# oc.net
KiCad netlist of a schematic drawn in EAGLE
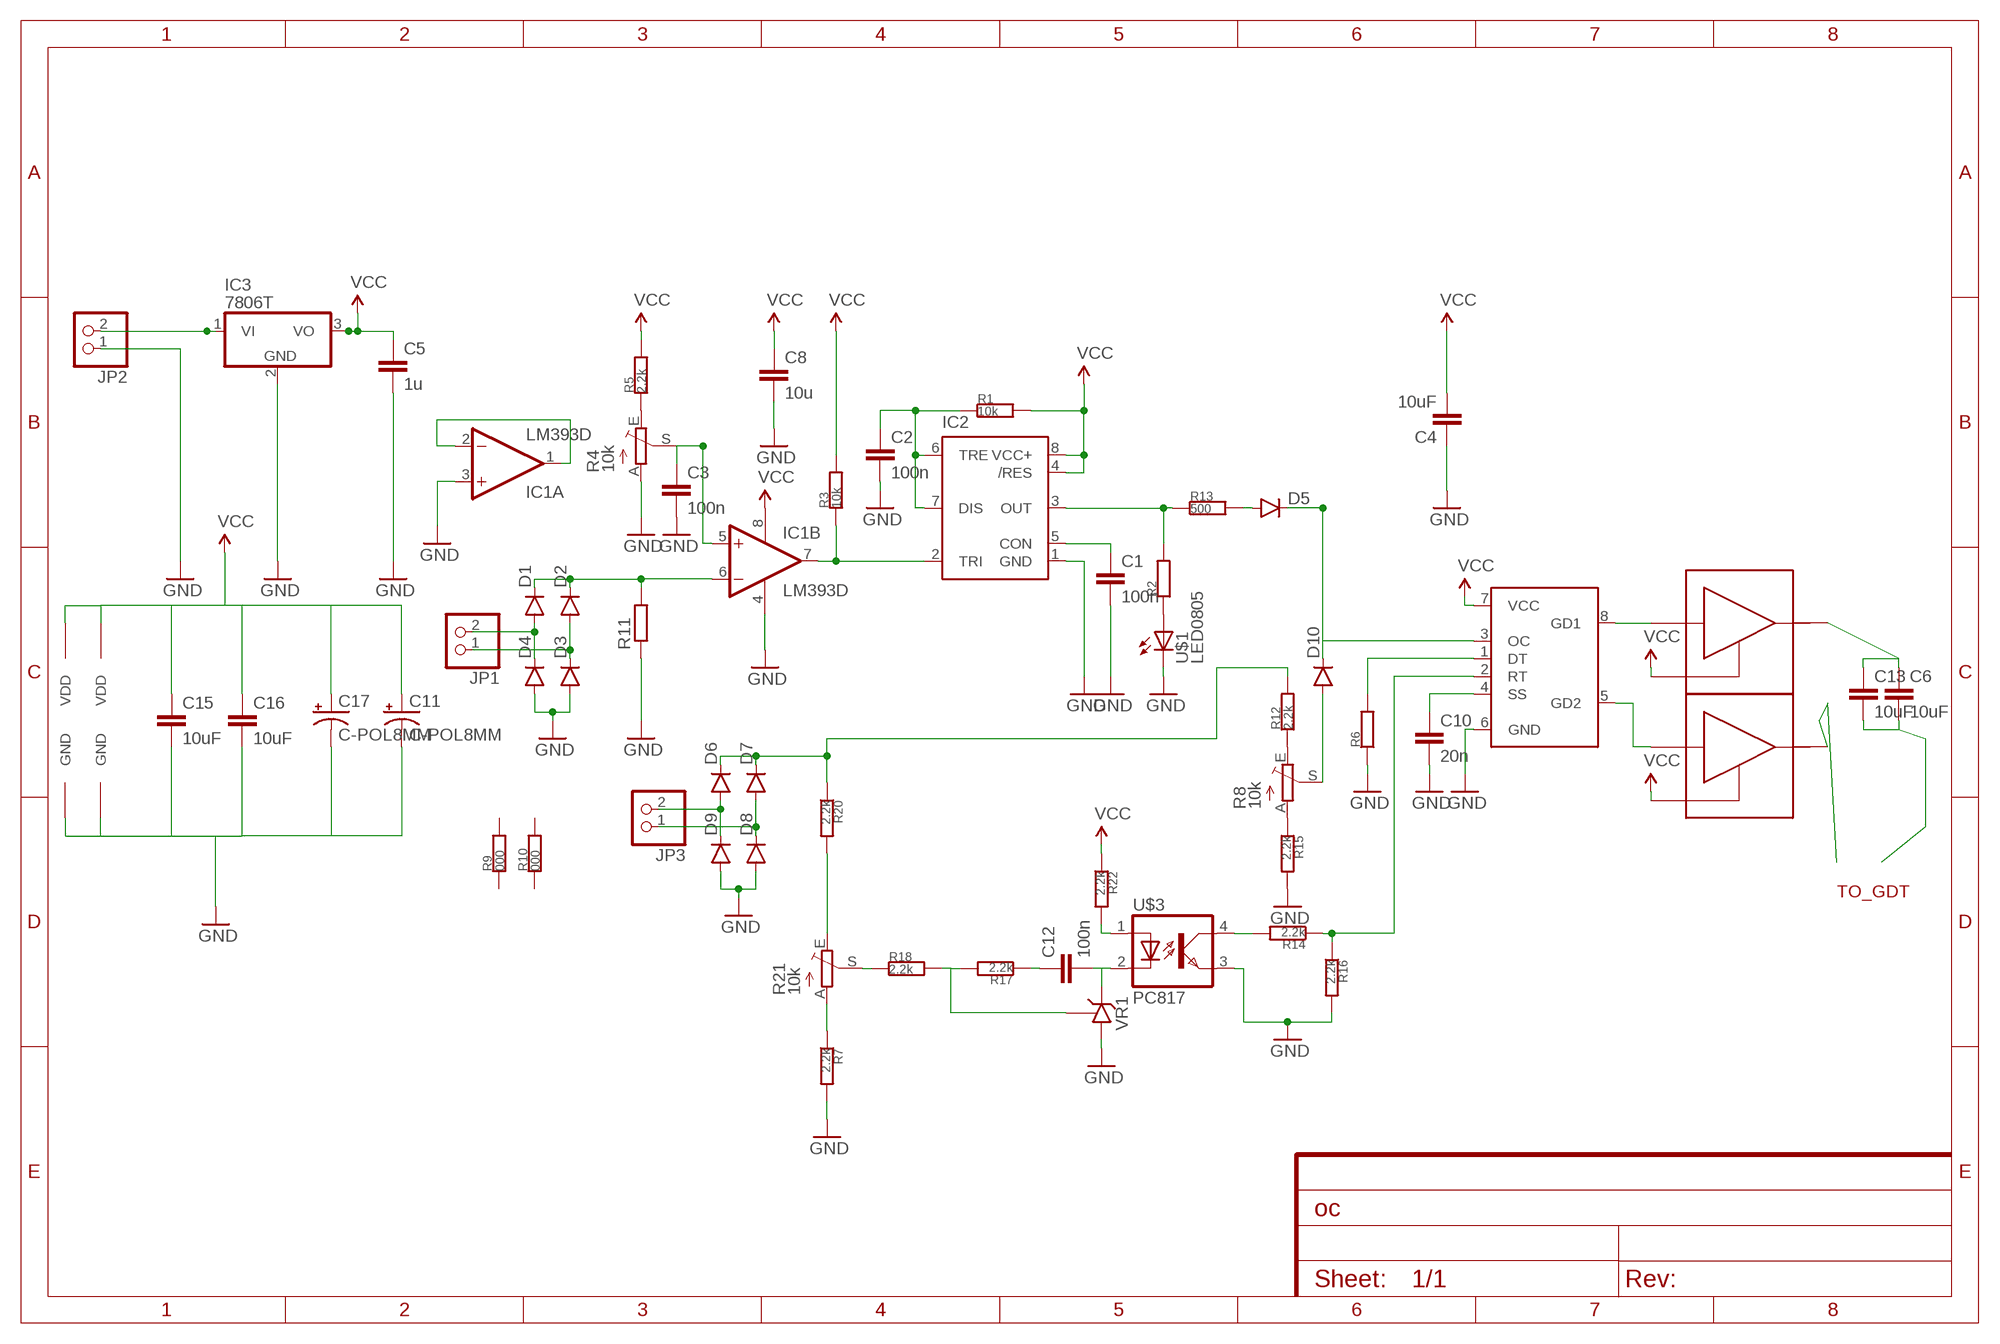
[diagram p0: schematic, sheet 1]

(export (version "E")
  (design (tool "Eeschema 10.0.6"))
  (components
    (comp (ref "C1")
      (value "100n")
      (footprint "eagle-import:C0805")
      (libsource (lib "eagle-import") (part "CC0805"))
    )
    (comp (ref "C2")
      (value "100n")
      (footprint "eagle-import:C0805")
      (libsource (lib "eagle-import") (part "CC0805"))
    )
    (comp (ref "C3")
      (value "100n")
      (footprint "eagle-import:C0603")
      (libsource (lib "eagle-import") (part "CC0603"))
    )
    (comp (ref "C4")
      (value "10uF")
      (footprint "eagle-import:1210")
      (libsource (lib "eagle-import") (part "10UF50V20%(1210)"))
    )
    (comp (ref "C5")
      (value "1u")
      (footprint "eagle-import:C0805")
      (libsource (lib "eagle-import") (part "CC0805"))
    )
    (comp (ref "C6")
      (value "10uF")
      (footprint "eagle-import:1210")
      (libsource (lib "eagle-import") (part "10UF50V20%(1210)"))
    )
    (comp (ref "C8")
      (value "10u")
      (footprint "eagle-import:C0805")
      (libsource (lib "eagle-import") (part "CC0805"))
    )
    (comp (ref "C10")
      (value "20n")
      (footprint "eagle-import:C0805")
      (libsource (lib "eagle-import") (part "CC0805"))
    )
    (comp (ref "C11")
      (value "C-POL8MM")
      (footprint "eagle-import:PCAP8")
      (libsource (lib "eagle-import") (part "C-POL8MM"))
    )
    (comp (ref "C12")
      (value "100n")
      (footprint "eagle-import:C0805")
      (libsource (lib "eagle-import") (part "CC0805"))
    )
    (comp (ref "C13")
      (value "10uF")
      (footprint "eagle-import:1210")
      (libsource (lib "eagle-import") (part "10UF50V20%(1210)"))
    )
    (comp (ref "C15")
      (value "10uF")
      (footprint "eagle-import:1210")
      (libsource (lib "eagle-import") (part "10UF50V20%(1210)"))
    )
    (comp (ref "C16")
      (value "10uF")
      (footprint "eagle-import:1210")
      (libsource (lib "eagle-import") (part "10UF50V20%(1210)"))
    )
    (comp (ref "C17")
      (value "C-POL8MM")
      (footprint "eagle-import:PCAP8")
      (libsource (lib "eagle-import") (part "C-POL8MM"))
    )
    (comp (ref "D1")
      (value "PMLL4150")
      (footprint "eagle-import:SOD80C")
      (libsource (lib "eagle-import") (part "PMLL4150"))
    )
    (comp (ref "D2")
      (value "PMLL4150")
      (footprint "eagle-import:SOD80C")
      (libsource (lib "eagle-import") (part "PMLL4150"))
    )
    (comp (ref "D3")
      (value "PMLL4150")
      (footprint "eagle-import:SOD80C")
      (libsource (lib "eagle-import") (part "PMLL4150"))
    )
    (comp (ref "D4")
      (value "PMLL4150")
      (footprint "eagle-import:SOD80C")
      (libsource (lib "eagle-import") (part "PMLL4150"))
    )
    (comp (ref "D5")
      (value "PMLL4150")
      (footprint "eagle-import:SOD80C")
      (libsource (lib "eagle-import") (part "PMLL4150"))
    )
    (comp (ref "D6")
      (value "PMLL4150")
      (footprint "eagle-import:SOD80C")
      (libsource (lib "eagle-import") (part "PMLL4150"))
    )
    (comp (ref "D7")
      (value "PMLL4150")
      (footprint "eagle-import:SOD80C")
      (libsource (lib "eagle-import") (part "PMLL4150"))
    )
    (comp (ref "D8")
      (value "PMLL4150")
      (footprint "eagle-import:SOD80C")
      (libsource (lib "eagle-import") (part "PMLL4150"))
    )
    (comp (ref "D9")
      (value "PMLL4150")
      (footprint "eagle-import:SOD80C")
      (libsource (lib "eagle-import") (part "PMLL4150"))
    )
    (comp (ref "D10")
      (value "PMLL4150")
      (footprint "eagle-import:SOD80C")
      (libsource (lib "eagle-import") (part "PMLL4150"))
    )
    (comp (ref "IC1")
      (value "LM393D")
      (footprint "eagle-import:SO08")
      (libsource (lib "eagle-import") (part "LM393D"))
    )
    (comp (ref "IC2")
      (value "NE555D")
      (footprint "eagle-import:SO08")
      (libsource (lib "eagle-import") (part "NE555D"))
    )
    (comp (ref "IC3")
      (value "7806T")
      (footprint "eagle-import:TO220H")
      (libsource (lib "eagle-import") (part "78T06"))
    )
    (comp (ref "JP1")
      (value "PINHD-1X2")
      (footprint "eagle-import:1X02")
      (libsource (lib "eagle-import") (part "PINHD-1X2"))
    )
    (comp (ref "JP2")
      (value "PINHD-1X2")
      (footprint "eagle-import:1X02")
      (libsource (lib "eagle-import") (part "PINHD-1X2"))
    )
    (comp (ref "JP3")
      (value "PINHD-1X2")
      (footprint "eagle-import:1X02")
      (libsource (lib "eagle-import") (part "PINHD-1X2"))
    )
    (comp (ref "R1")
      (value "10k")
      (footprint "eagle-import:R0805")
      (libsource (lib "eagle-import") (part "R0805"))
    )
    (comp (ref "R2")
      (value "R0805")
      (footprint "eagle-import:R0805")
      (libsource (lib "eagle-import") (part "R0805"))
    )
    (comp (ref "R3")
      (value "10k")
      (footprint "eagle-import:R0805")
      (libsource (lib "eagle-import") (part "R0805"))
    )
    (comp (ref "R4")
      (value "10k")
      (footprint "eagle-import:RJ9W")
      (libsource (lib "eagle-import") (part "TRIM_EU-RJ9W"))
    )
    (comp (ref "R5")
      (value "2.2k")
      (footprint "eagle-import:R0805")
      (libsource (lib "eagle-import") (part "R0805"))
    )
    (comp (ref "R6")
      (value "R0805")
      (footprint "eagle-import:R0805")
      (libsource (lib "eagle-import") (part "R0805"))
    )
    (comp (ref "R7")
      (value "2.2k")
      (footprint "eagle-import:R0805")
      (libsource (lib "eagle-import") (part "R0805"))
    )
    (comp (ref "R8")
      (value "10k")
      (footprint "eagle-import:RJ9W")
      (libsource (lib "eagle-import") (part "TRIM_EU-RJ9W"))
    )
    (comp (ref "R9")
      (value "000")
      (footprint "eagle-import:R1206")
      (libsource (lib "eagle-import") (part "R1206"))
    )
    (comp (ref "R10")
      (value "000")
      (footprint "eagle-import:R0805")
      (libsource (lib "eagle-import") (part "R0805"))
    )
    (comp (ref "R11")
      (value "R-EU_0617/17")
      (footprint "eagle-import:0617_17")
      (libsource (lib "eagle-import") (part "R-EU_0617/17"))
    )
    (comp (ref "R12")
      (value "2.2k")
      (footprint "eagle-import:R0805")
      (libsource (lib "eagle-import") (part "R0805"))
    )
    (comp (ref "R13")
      (value "500")
      (footprint "eagle-import:R0805")
      (libsource (lib "eagle-import") (part "R0805"))
    )
    (comp (ref "R14")
      (value "2.2k")
      (footprint "eagle-import:R0805")
      (libsource (lib "eagle-import") (part "R0805"))
    )
    (comp (ref "R15")
      (value "2.2k")
      (footprint "eagle-import:R0805")
      (libsource (lib "eagle-import") (part "R0805"))
    )
    (comp (ref "R16")
      (value "2.2k")
      (footprint "eagle-import:R0805")
      (libsource (lib "eagle-import") (part "R0805"))
    )
    (comp (ref "R17")
      (value "2.2k")
      (footprint "eagle-import:R0805")
      (libsource (lib "eagle-import") (part "R0805"))
    )
    (comp (ref "R18")
      (value "2.2k")
      (footprint "eagle-import:R0805")
      (libsource (lib "eagle-import") (part "R0805"))
    )
    (comp (ref "R20")
      (value "2.2k")
      (footprint "eagle-import:R0805")
      (libsource (lib "eagle-import") (part "R0805"))
    )
    (comp (ref "R21")
      (value "10k")
      (footprint "eagle-import:RJ9W")
      (libsource (lib "eagle-import") (part "TRIM_EU-RJ9W"))
    )
    (comp (ref "R22")
      (value "2.2k")
      (footprint "eagle-import:R0805")
      (libsource (lib "eagle-import") (part "R0805"))
    )
    (comp (ref "U$1")
      (value "LED0805")
      (footprint "eagle-import:0805-LED")
      (libsource (lib "eagle-import") (part "LED0805"))
    )
    (comp (ref "U$2")
      (value "TPS92020")
      (footprint "eagle-import:SO08")
      (libsource (lib "eagle-import") (part "TPS92020"))
    )
    (comp (ref "U$3")
      (value "PC817")
      (footprint "eagle-import:DIL4-SMD")
      (libsource (lib "eagle-import") (part "PC817"))
    )
    (comp (ref "U$7")
      (value "IXDD614")
      (footprint "eagle-import:DPACK-5")
      (libsource (lib "eagle-import") (part "IXDD614"))
    )
    (comp (ref "U$8")
      (value "IXDD614")
      (footprint "eagle-import:DPACK-5")
      (libsource (lib "eagle-import") (part "IXDD614"))
    )
    (comp (ref "VR1")
      (value "TL431CLPSO8")
      (footprint "eagle-import:SO08")
      (libsource (lib "eagle-import") (part "TL431CLPSO8"))
    )
  )
  (nets
    (net (code "1") (name "GND") (class "Default")
      (node (ref "C1") (pin "2") (pinfunction "2_2") (pintype "passive"))
      (node (ref "C10") (pin "2") (pinfunction "2_2") (pintype "passive"))
      (node (ref "C11") (pin "P$2") (pinfunction "-_P$2") (pintype "passive"))
      (node (ref "C15") (pin "2") (pinfunction "2_2") (pintype "passive"))
      (node (ref "C16") (pin "2") (pinfunction "2_2") (pintype "passive"))
      (node (ref "C17") (pin "P$2") (pinfunction "-_P$2") (pintype "passive"))
      (node (ref "C2") (pin "2") (pinfunction "2_2") (pintype "passive"))
      (node (ref "C3") (pin "2") (pinfunction "2_2") (pintype "passive"))
      (node (ref "C4") (pin "1") (pinfunction "1_1") (pintype "passive"))
      (node (ref "C5") (pin "2") (pinfunction "2_2") (pintype "passive"))
      (node (ref "C8") (pin "2") (pinfunction "2_2") (pintype "passive"))
      (node (ref "D3") (pin "A") (pinfunction "A_A") (pintype "passive"))
      (node (ref "D4") (pin "A") (pinfunction "A_A") (pintype "passive"))
      (node (ref "D8") (pin "A") (pinfunction "A_A") (pintype "passive"))
      (node (ref "D9") (pin "A") (pinfunction "A_A") (pintype "passive"))
      (node (ref "IC1") (pin "3") (pinfunction "+IN_3") (pintype "input"))
      (node (ref "IC1") (pin "4") (pinfunction "V-_4") (pintype "power_in"))
      (node (ref "IC2") (pin "1") (pinfunction "GND_1") (pintype "power_in"))
      (node (ref "IC3") (pin "2") (pinfunction "GND_2") (pintype "passive"))
      (node (ref "JP2") (pin "1") (pinfunction "1_1") (pintype "passive"))
      (node (ref "R11") (pin "1") (pinfunction "1_1") (pintype "passive"))
      (node (ref "R15") (pin "2") (pinfunction "2_2") (pintype "passive"))
      (node (ref "R16") (pin "2") (pinfunction "2_2") (pintype "passive"))
      (node (ref "R4") (pin "A") (pinfunction "A_A") (pintype "passive"))
      (node (ref "R6") (pin "1") (pinfunction "1_1") (pintype "passive"))
      (node (ref "R7") (pin "2") (pinfunction "2_2") (pintype "passive"))
      (node (ref "U$1") (pin "C") (pinfunction "C_C") (pintype "passive"))
      (node (ref "U$2") (pin "6") (pinfunction "GND_6") (pintype "bidirectional"))
      (node (ref "U$3") (pin "3") (pinfunction "EMIT_3") (pintype "passive"))
      (node (ref "U$7") (pin "3") (pinfunction "GND_3") (pintype "power_in"))
      (node (ref "U$7") (pin "6") (pinfunction "GND_6") (pintype "power_in"))
      (node (ref "U$8") (pin "3") (pinfunction "GND_3") (pintype "power_in"))
      (node (ref "U$8") (pin "6") (pinfunction "GND_6") (pintype "power_in"))
      (node (ref "VR1") (pin "2") (pinfunction "A_2") (pintype "passive"))
      (node (ref "VR1") (pin "3") (pinfunction "A_3") (pintype "passive"))
      (node (ref "VR1") (pin "6") (pinfunction "A_6") (pintype "passive"))
      (node (ref "VR1") (pin "7") (pinfunction "A_7") (pintype "passive"))
    )
    (net (code "2") (name "Net-(C12-Pad1)") (class "Default")
      (node (ref "C12") (pin "1") (pinfunction "1_1") (pintype "passive"))
      (node (ref "R17") (pin "1") (pinfunction "1_1") (pintype "passive"))
    )
    (net (code "3") (name "Net-(C13-Pad2)") (class "Default")
      (node (ref "C13") (pin "2") (pinfunction "2_2") (pintype "passive"))
      (node (ref "C6") (pin "2") (pinfunction "2_2") (pintype "passive"))
    )
    (net (code "4") (name "Net-(D1-PadA)") (class "Default")
      (node (ref "D1") (pin "A") (pinfunction "A_A") (pintype "passive"))
      (node (ref "D4") (pin "C") (pinfunction "C_C") (pintype "passive"))
      (node (ref "JP1") (pin "2") (pinfunction "2_2") (pintype "passive"))
    )
    (net (code "5") (name "Net-(D2-PadA)") (class "Default")
      (node (ref "D2") (pin "A") (pinfunction "A_A") (pintype "passive"))
      (node (ref "D3") (pin "C") (pinfunction "C_C") (pintype "passive"))
      (node (ref "JP1") (pin "1") (pinfunction "1_1") (pintype "passive"))
    )
    (net (code "6") (name "Net-(D5-PadA)") (class "Default")
      (node (ref "D5") (pin "A") (pinfunction "A_A") (pintype "passive"))
      (node (ref "R13") (pin "2") (pinfunction "2_2") (pintype "passive"))
    )
    (net (code "7") (name "Net-(D6-PadA)") (class "Default")
      (node (ref "D6") (pin "A") (pinfunction "A_A") (pintype "passive"))
      (node (ref "D9") (pin "C") (pinfunction "C_C") (pintype "passive"))
      (node (ref "JP3") (pin "2") (pinfunction "2_2") (pintype "passive"))
    )
    (net (code "8") (name "Net-(D6-PadC)") (class "Default")
      (node (ref "D6") (pin "C") (pinfunction "C_C") (pintype "passive"))
      (node (ref "D7") (pin "C") (pinfunction "C_C") (pintype "passive"))
      (node (ref "R12") (pin "2") (pinfunction "2_2") (pintype "passive"))
      (node (ref "R20") (pin "1") (pinfunction "1_1") (pintype "passive"))
    )
    (net (code "9") (name "Net-(D7-PadA)") (class "Default")
      (node (ref "D7") (pin "A") (pinfunction "A_A") (pintype "passive"))
      (node (ref "D8") (pin "C") (pinfunction "C_C") (pintype "passive"))
      (node (ref "JP3") (pin "1") (pinfunction "1_1") (pintype "passive"))
    )
    (net (code "10") (name "Net-(D10-PadA)") (class "Default")
      (node (ref "D10") (pin "A") (pinfunction "A_A") (pintype "passive"))
      (node (ref "R8") (pin "S") (pinfunction "S_S") (pintype "passive"))
    )
    (net (code "11") (name "Net-(IC1A--IN)") (class "Default")
      (node (ref "IC1") (pin "1") (pinfunction "OUT_1") (pintype "output"))
      (node (ref "IC1") (pin "2") (pinfunction "-IN_2") (pintype "input"))
    )
    (net (code "12") (name "Net-(IC1B-+IN)") (class "Default")
      (node (ref "C3") (pin "1") (pinfunction "1_1") (pintype "passive"))
      (node (ref "IC1") (pin "5") (pinfunction "+IN_5") (pintype "input"))
      (node (ref "R4") (pin "S") (pinfunction "S_S") (pintype "passive"))
    )
    (net (code "13") (name "Net-(IC1B--IN)") (class "Default")
      (node (ref "D1") (pin "C") (pinfunction "C_C") (pintype "passive"))
      (node (ref "D2") (pin "C") (pinfunction "C_C") (pintype "passive"))
      (node (ref "IC1") (pin "6") (pinfunction "-IN_6") (pintype "input"))
      (node (ref "R11") (pin "2") (pinfunction "2_2") (pintype "passive"))
    )
    (net (code "14") (name "Net-(IC1B-OUT)") (class "Default")
      (node (ref "IC1") (pin "7") (pinfunction "OUT_7") (pintype "output"))
      (node (ref "IC2") (pin "2") (pinfunction "TRI_2") (pintype "input"))
      (node (ref "R3") (pin "1") (pinfunction "1_1") (pintype "passive"))
    )
    (net (code "15") (name "Net-(IC2-CON)") (class "Default")
      (node (ref "C1") (pin "1") (pinfunction "1_1") (pintype "passive"))
      (node (ref "IC2") (pin "5") (pinfunction "CON_5") (pintype "input"))
    )
    (net (code "16") (name "Net-(IC2-DIS)") (class "Default")
      (node (ref "C2") (pin "1") (pinfunction "1_1") (pintype "passive"))
      (node (ref "IC2") (pin "6") (pinfunction "TRE_6") (pintype "input"))
      (node (ref "IC2") (pin "7") (pinfunction "DIS_7") (pintype "input"))
      (node (ref "R1") (pin "1") (pinfunction "1_1") (pintype "passive"))
    )
    (net (code "17") (name "Net-(IC2-OUT)") (class "Default")
      (node (ref "IC2") (pin "3") (pinfunction "OUT_3") (pintype "output"))
      (node (ref "R13") (pin "1") (pinfunction "1_1") (pintype "passive"))
      (node (ref "R2") (pin "2") (pinfunction "2_2") (pintype "passive"))
    )
    (net (code "18") (name "Net-(IC3-VI)") (class "Default")
      (node (ref "IC3") (pin "1") (pinfunction "VI_1") (pintype "input"))
      (node (ref "JP2") (pin "2") (pinfunction "2_2") (pintype "passive"))
    )
    (net (code "19") (name "Net-(R2-Pad1)") (class "Default")
      (node (ref "R2") (pin "1") (pinfunction "1_1") (pintype "passive"))
      (node (ref "U$1") (pin "A") (pinfunction "A_A") (pintype "passive"))
    )
    (net (code "20") (name "Net-(R4-PadE)") (class "Default")
      (node (ref "R4") (pin "E") (pinfunction "E_E") (pintype "passive"))
      (node (ref "R5") (pin "1") (pinfunction "1_1") (pintype "passive"))
    )
    (net (code "21") (name "Net-(R12-Pad1)") (class "Default")
      (node (ref "R12") (pin "1") (pinfunction "1_1") (pintype "passive"))
      (node (ref "R8") (pin "E") (pinfunction "E_E") (pintype "passive"))
    )
    (net (code "22") (name "Net-(R15-Pad1)") (class "Default")
      (node (ref "R15") (pin "1") (pinfunction "1_1") (pintype "passive"))
      (node (ref "R8") (pin "A") (pinfunction "A_A") (pintype "passive"))
    )
    (net (code "23") (name "Net-(R18-Pad1)") (class "Default")
      (node (ref "R18") (pin "1") (pinfunction "1_1") (pintype "passive"))
      (node (ref "R21") (pin "S") (pinfunction "S_S") (pintype "passive"))
    )
    (net (code "24") (name "Net-(R20-Pad2)") (class "Default")
      (node (ref "R20") (pin "2") (pinfunction "2_2") (pintype "passive"))
      (node (ref "R21") (pin "E") (pinfunction "E_E") (pintype "passive"))
    )
    (net (code "25") (name "Net-(R21-PadA)") (class "Default")
      (node (ref "R21") (pin "A") (pinfunction "A_A") (pintype "passive"))
      (node (ref "R7") (pin "1") (pinfunction "1_1") (pintype "passive"))
    )
    (net (code "26") (name "Net-(U$2-DT)") (class "Default")
      (node (ref "R6") (pin "2") (pinfunction "2_2") (pintype "passive"))
      (node (ref "U$2") (pin "1") (pinfunction "DT_1") (pintype "bidirectional"))
    )
    (net (code "27") (name "Net-(U$2-GD1)") (class "Default")
      (node (ref "U$2") (pin "8") (pinfunction "GD1_8") (pintype "bidirectional"))
      (node (ref "U$8") (pin "4") (pinfunction "IN_4") (pintype "bidirectional"))
    )
    (net (code "28") (name "Net-(U$2-GD2)") (class "Default")
      (node (ref "U$2") (pin "5") (pinfunction "GD2_5") (pintype "bidirectional"))
      (node (ref "U$7") (pin "4") (pinfunction "IN_4") (pintype "bidirectional"))
    )
    (net (code "29") (name "Net-(U$2-OC)") (class "Default")
      (node (ref "D10") (pin "C") (pinfunction "C_C") (pintype "passive"))
      (node (ref "D5") (pin "C") (pinfunction "C_C") (pintype "passive"))
      (node (ref "U$2") (pin "3") (pinfunction "OC_3") (pintype "bidirectional"))
    )
    (net (code "30") (name "Net-(U$2-RT)") (class "Default")
      (node (ref "R14") (pin "1") (pinfunction "1_1") (pintype "passive"))
      (node (ref "R16") (pin "1") (pinfunction "1_1") (pintype "passive"))
      (node (ref "U$2") (pin "2") (pinfunction "RT_2") (pintype "bidirectional"))
    )
    (net (code "31") (name "Net-(U$2-SS)") (class "Default")
      (node (ref "C10") (pin "1") (pinfunction "1_1") (pintype "passive"))
      (node (ref "U$2") (pin "4") (pinfunction "SS_4") (pintype "bidirectional"))
    )
    (net (code "32") (name "Net-(U$3-A)") (class "Default")
      (node (ref "R22") (pin "2") (pinfunction "2_2") (pintype "passive"))
      (node (ref "U$3") (pin "1") (pinfunction "A_1") (pintype "passive"))
    )
    (net (code "33") (name "Net-(U$3-C)") (class "Default")
      (node (ref "C12") (pin "2") (pinfunction "2_2") (pintype "passive"))
      (node (ref "U$3") (pin "2") (pinfunction "C_2") (pintype "passive"))
      (node (ref "VR1") (pin "1") (pinfunction "C_1") (pintype "passive"))
    )
    (net (code "34") (name "Net-(U$3-COL)") (class "Default")
      (node (ref "R14") (pin "2") (pinfunction "2_2") (pintype "passive"))
      (node (ref "U$3") (pin "4") (pinfunction "COL_4") (pintype "passive"))
    )
    (net (code "35") (name "Net-(U$8A-OUT)") (class "Default")
      (node (ref "C13") (pin "1") (pinfunction "1_1") (pintype "passive"))
      (node (ref "C6") (pin "1") (pinfunction "1_1") (pintype "passive"))
      (node (ref "U$8") (pin "2") (pinfunction "OUT_2") (pintype "bidirectional"))
    )
    (net (code "36") (name "Net-(VR1-R)") (class "Default")
      (node (ref "R17") (pin "2") (pinfunction "2_2") (pintype "passive"))
      (node (ref "R18") (pin "2") (pinfunction "2_2") (pintype "passive"))
      (node (ref "VR1") (pin "8") (pinfunction "R_8") (pintype "passive"))
    )
    (net (code "37") (name "VCC") (class "Default")
      (node (ref "C11") (pin "P$1") (pinfunction "+_P$1") (pintype "passive"))
      (node (ref "C15") (pin "1") (pinfunction "1_1") (pintype "passive"))
      (node (ref "C16") (pin "1") (pinfunction "1_1") (pintype "passive"))
      (node (ref "C17") (pin "P$1") (pinfunction "+_P$1") (pintype "passive"))
      (node (ref "C4") (pin "2") (pinfunction "2_2") (pintype "passive"))
      (node (ref "C5") (pin "1") (pinfunction "1_1") (pintype "passive"))
      (node (ref "C8") (pin "1") (pinfunction "1_1") (pintype "passive"))
      (node (ref "IC1") (pin "8") (pinfunction "V+_8") (pintype "power_in"))
      (node (ref "IC2") (pin "4") (pinfunction "/RES_4") (pintype "input"))
      (node (ref "IC2") (pin "8") (pinfunction "VCC+_8") (pintype "power_in"))
      (node (ref "IC3") (pin "3") (pinfunction "VO_3") (pintype "passive"))
      (node (ref "R1") (pin "2") (pinfunction "2_2") (pintype "passive"))
      (node (ref "R22") (pin "1") (pinfunction "1_1") (pintype "passive"))
      (node (ref "R3") (pin "2") (pinfunction "2_2") (pintype "passive"))
      (node (ref "R5") (pin "2") (pinfunction "2_2") (pintype "passive"))
      (node (ref "U$2") (pin "7") (pinfunction "VCC_7") (pintype "bidirectional"))
      (node (ref "U$7") (pin "1") (pinfunction "VDD_1") (pintype "power_in"))
      (node (ref "U$7") (pin "5") (pinfunction "EN_5") (pintype "bidirectional"))
      (node (ref "U$8") (pin "1") (pinfunction "VDD_1") (pintype "power_in"))
      (node (ref "U$8") (pin "5") (pinfunction "EN_5") (pintype "bidirectional"))
    )
    (net (code "38") (name "unconnected-(R9-Pad1)") (class "Default")
      (node (ref "R9") (pin "1") (pinfunction "1_1") (pintype "passive"))
    )
    (net (code "39") (name "unconnected-(R9-Pad2)") (class "Default")
      (node (ref "R9") (pin "2") (pinfunction "2_2") (pintype "passive"))
    )
    (net (code "40") (name "unconnected-(R10-Pad1)") (class "Default")
      (node (ref "R10") (pin "1") (pinfunction "1_1") (pintype "passive"))
    )
    (net (code "41") (name "unconnected-(R10-Pad2)") (class "Default")
      (node (ref "R10") (pin "2") (pinfunction "2_2") (pintype "passive"))
    )
    (net (code "42") (name "unconnected-(U$7A-OUT-Pad2)") (class "Default")
      (node (ref "U$7") (pin "2") (pinfunction "OUT_2") (pintype "bidirectional"))
    )
  )
)
